# fretscanner-BRAIN.net
KiCad netlist of a schematic drawn in EAGLE
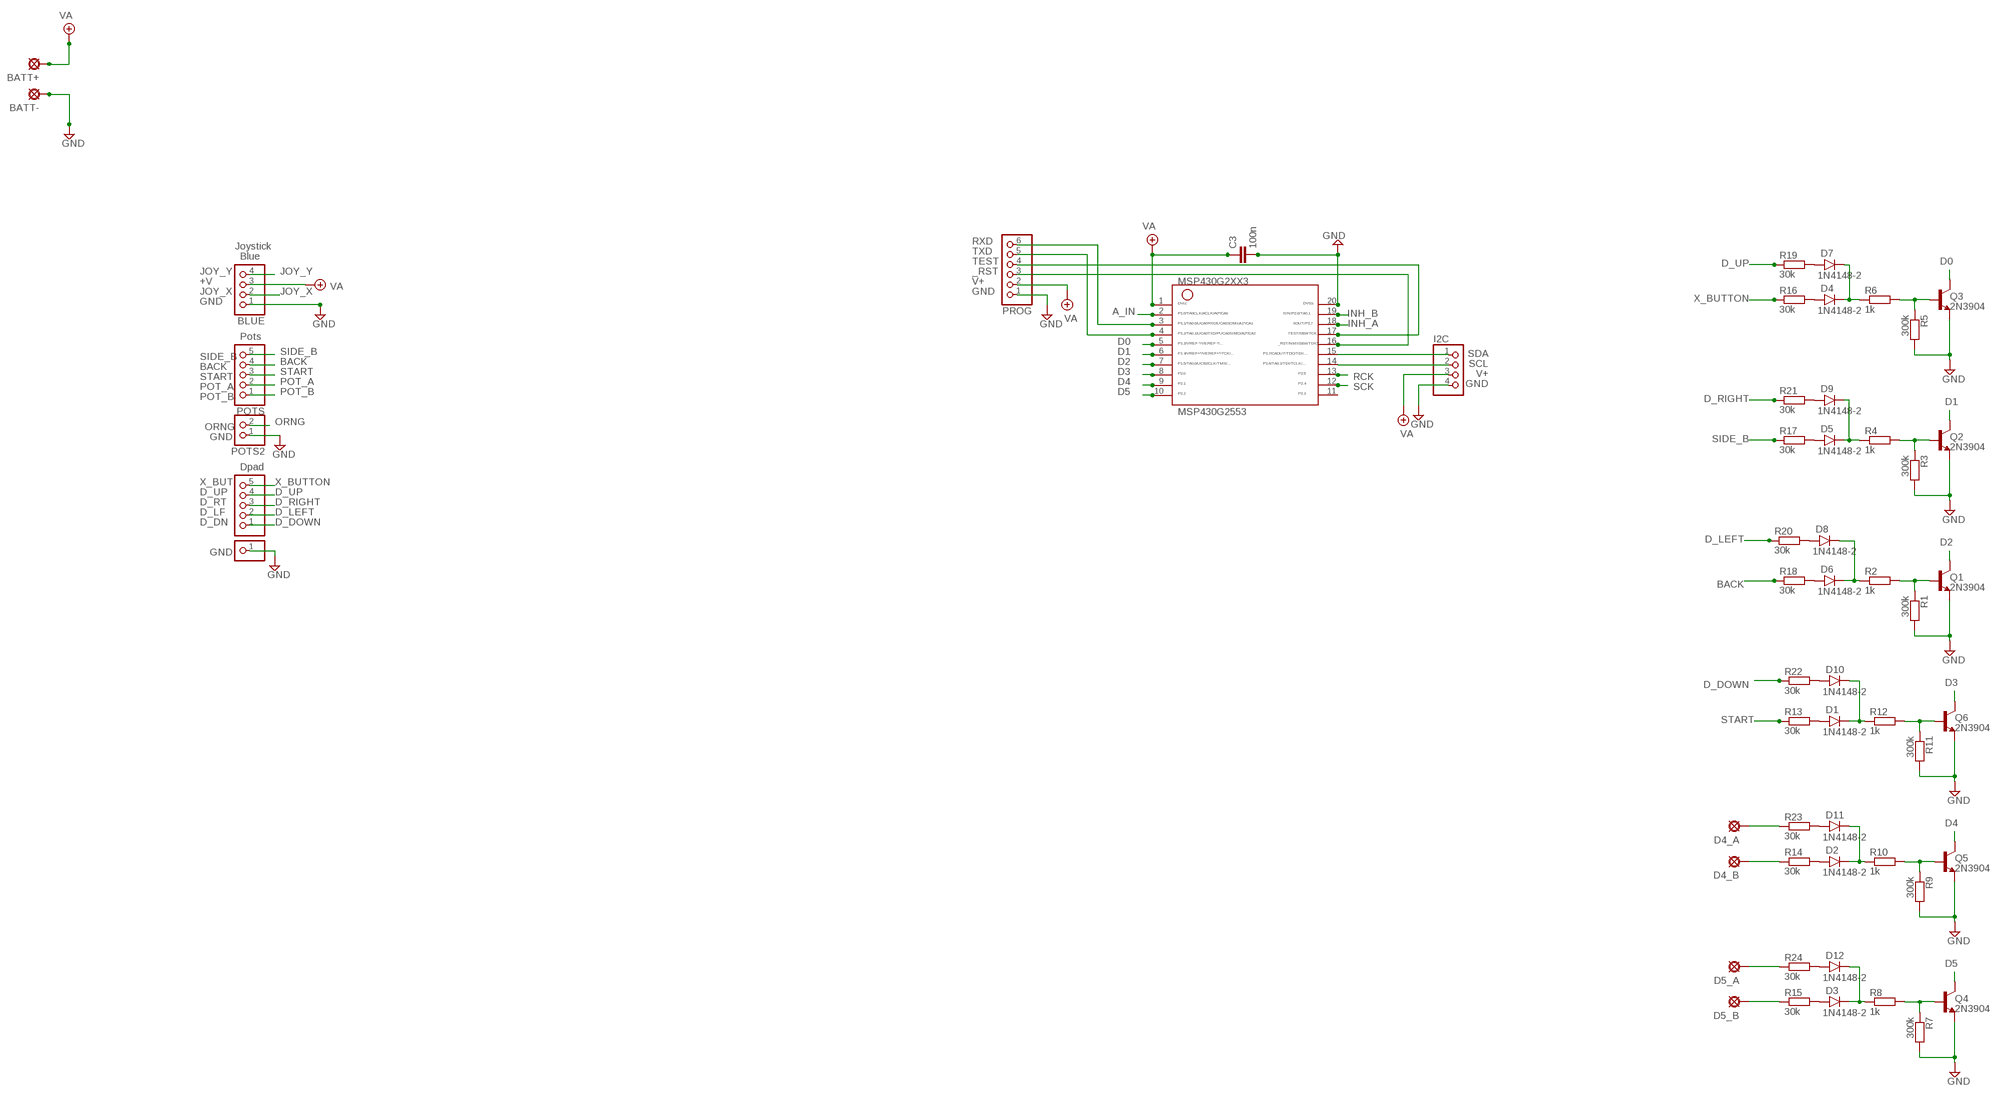
[diagram p0: schematic, sheet 1]

(export (version "E")
  (design (tool "Eeschema 10.0.6"))
  (components
    (comp (ref "BATT+")
      (value "PADL")
      (footprint "eagle-import:LONG")
      (libsource (lib "eagle-import") (part "PADL"))
    )
    (comp (ref "BATT-")
      (value "PADL")
      (footprint "eagle-import:LONG")
      (libsource (lib "eagle-import") (part "PADL"))
    )
    (comp (ref "BLUE")
      (value "PINHD-1X4")
      (footprint "eagle-import:1X04")
      (libsource (lib "eagle-import") (part "PINHD-1X4"))
    )
    (comp (ref "C3")
      (value "100n")
      (footprint "eagle-import:050X030_050_3")
      (libsource (lib "eagle-import") (part "050X030_050"))
    )
    (comp (ref "D1")
      (value "1N4148-2")
      (footprint "eagle-import:DO35-2")
      (libsource (lib "eagle-import") (part "1N4148-2"))
    )
    (comp (ref "D2")
      (value "1N4148-2")
      (footprint "eagle-import:DO35-2")
      (libsource (lib "eagle-import") (part "1N4148-2"))
    )
    (comp (ref "D3")
      (value "1N4148-2")
      (footprint "eagle-import:DO35-2")
      (libsource (lib "eagle-import") (part "1N4148-2"))
    )
    (comp (ref "D4")
      (value "1N4148-2")
      (footprint "eagle-import:DO35-2")
      (libsource (lib "eagle-import") (part "1N4148-2"))
    )
    (comp (ref "D4_A")
      (value "PAD")
      (footprint "eagle-import:SQUARE")
      (libsource (lib "eagle-import") (part "PAD"))
    )
    (comp (ref "D4_B")
      (value "PAD")
      (footprint "eagle-import:SQUARE")
      (libsource (lib "eagle-import") (part "PAD"))
    )
    (comp (ref "D5")
      (value "1N4148-2")
      (footprint "eagle-import:DO35-2")
      (libsource (lib "eagle-import") (part "1N4148-2"))
    )
    (comp (ref "D5_A")
      (value "PAD")
      (footprint "eagle-import:SQUARE")
      (libsource (lib "eagle-import") (part "PAD"))
    )
    (comp (ref "D5_B")
      (value "PAD")
      (footprint "eagle-import:SQUARE")
      (libsource (lib "eagle-import") (part "PAD"))
    )
    (comp (ref "D6")
      (value "1N4148-2")
      (footprint "eagle-import:DO35-2")
      (libsource (lib "eagle-import") (part "1N4148-2"))
    )
    (comp (ref "D7")
      (value "1N4148-2")
      (footprint "eagle-import:DO35-2")
      (libsource (lib "eagle-import") (part "1N4148-2"))
    )
    (comp (ref "D8")
      (value "1N4148-2")
      (footprint "eagle-import:DO35-2")
      (libsource (lib "eagle-import") (part "1N4148-2"))
    )
    (comp (ref "D9")
      (value "1N4148-2")
      (footprint "eagle-import:DO35-2")
      (libsource (lib "eagle-import") (part "1N4148-2"))
    )
    (comp (ref "D10")
      (value "1N4148-2")
      (footprint "eagle-import:DO35-2")
      (libsource (lib "eagle-import") (part "1N4148-2"))
    )
    (comp (ref "D11")
      (value "1N4148-2")
      (footprint "eagle-import:DO35-2")
      (libsource (lib "eagle-import") (part "1N4148-2"))
    )
    (comp (ref "D12")
      (value "1N4148-2")
      (footprint "eagle-import:DO35-2")
      (libsource (lib "eagle-import") (part "1N4148-2"))
    )
    (comp (ref "DPAD")
      (value "PINHD-1X5")
      (footprint "eagle-import:1X05")
      (libsource (lib "eagle-import") (part "PINHD-1X5"))
    )
    (comp (ref "DPAD2")
      (value "PINHD-1X1")
      (footprint "eagle-import:1X01")
      (libsource (lib "eagle-import") (part "PINHD-1X1"))
    )
    (comp (ref "I2C")
      (value "PINHD-1X4")
      (footprint "eagle-import:1X04")
      (libsource (lib "eagle-import") (part "PINHD-1X4"))
    )
    (comp (ref "MSP430G2553")
      (value "G2XX3---N20")
      (footprint "eagle-import:N20")
      (libsource (lib "eagle-import") (part "G2XX3---N20"))
    )
    (comp (ref "POTS")
      (value "PINHD-1X5")
      (footprint "eagle-import:1X05")
      (libsource (lib "eagle-import") (part "PINHD-1X5"))
    )
    (comp (ref "POTS2")
      (value "PINHD-1X2")
      (footprint "eagle-import:1X02")
      (libsource (lib "eagle-import") (part "PINHD-1X2"))
    )
    (comp (ref "PROG")
      (value "PINHD-1X6")
      (footprint "eagle-import:1X06")
      (libsource (lib "eagle-import") (part "PINHD-1X6"))
    )
    (comp (ref "Q1")
      (value "2N3904")
      (footprint "eagle-import:TO92-")
      (libsource (lib "eagle-import") (part "2N3904"))
    )
    (comp (ref "Q2")
      (value "2N3904")
      (footprint "eagle-import:TO92-")
      (libsource (lib "eagle-import") (part "2N3904"))
    )
    (comp (ref "Q3")
      (value "2N3904")
      (footprint "eagle-import:TO92-")
      (libsource (lib "eagle-import") (part "2N3904"))
    )
    (comp (ref "Q4")
      (value "2N3904")
      (footprint "eagle-import:TO92-")
      (libsource (lib "eagle-import") (part "2N3904"))
    )
    (comp (ref "Q5")
      (value "2N3904")
      (footprint "eagle-import:TO92-")
      (libsource (lib "eagle-import") (part "2N3904"))
    )
    (comp (ref "Q6")
      (value "2N3904")
      (footprint "eagle-import:TO92-")
      (libsource (lib "eagle-import") (part "2N3904"))
    )
    (comp (ref "R1")
      (value "300k")
      (footprint "eagle-import:R0207_1V")
      (libsource (lib "eagle-import") (part "6MM-EU1"))
    )
    (comp (ref "R2")
      (value "1k")
      (footprint "eagle-import:R0207_3")
      (libsource (lib "eagle-import") (part "6MM-EU"))
    )
    (comp (ref "R3")
      (value "300k")
      (footprint "eagle-import:R0207_1V")
      (libsource (lib "eagle-import") (part "6MM-EU1"))
    )
    (comp (ref "R4")
      (value "1k")
      (footprint "eagle-import:R0207_3")
      (libsource (lib "eagle-import") (part "6MM-EU"))
    )
    (comp (ref "R5")
      (value "300k")
      (footprint "eagle-import:R0207_1V")
      (libsource (lib "eagle-import") (part "6MM-EU1"))
    )
    (comp (ref "R6")
      (value "1k")
      (footprint "eagle-import:R0207_3")
      (libsource (lib "eagle-import") (part "6MM-EU"))
    )
    (comp (ref "R7")
      (value "300k")
      (footprint "eagle-import:R0207_1V")
      (libsource (lib "eagle-import") (part "6MM-EU1"))
    )
    (comp (ref "R8")
      (value "1k")
      (footprint "eagle-import:R0207_3")
      (libsource (lib "eagle-import") (part "6MM-EU"))
    )
    (comp (ref "R9")
      (value "300k")
      (footprint "eagle-import:R0207_1V")
      (libsource (lib "eagle-import") (part "6MM-EU1"))
    )
    (comp (ref "R10")
      (value "1k")
      (footprint "eagle-import:R0207_3")
      (libsource (lib "eagle-import") (part "6MM-EU"))
    )
    (comp (ref "R11")
      (value "300k")
      (footprint "eagle-import:R0207_1V")
      (libsource (lib "eagle-import") (part "6MM-EU1"))
    )
    (comp (ref "R12")
      (value "1k")
      (footprint "eagle-import:R0207_3")
      (libsource (lib "eagle-import") (part "6MM-EU"))
    )
    (comp (ref "R13")
      (value "30k")
      (footprint "eagle-import:R0207_3")
      (libsource (lib "eagle-import") (part "6MM-EU"))
    )
    (comp (ref "R14")
      (value "30k")
      (footprint "eagle-import:R0207_3")
      (libsource (lib "eagle-import") (part "6MM-EU"))
    )
    (comp (ref "R15")
      (value "30k")
      (footprint "eagle-import:R0207_3")
      (libsource (lib "eagle-import") (part "6MM-EU"))
    )
    (comp (ref "R16")
      (value "30k")
      (footprint "eagle-import:R0207_3")
      (libsource (lib "eagle-import") (part "6MM-EU"))
    )
    (comp (ref "R17")
      (value "30k")
      (footprint "eagle-import:R0207_3")
      (libsource (lib "eagle-import") (part "6MM-EU"))
    )
    (comp (ref "R18")
      (value "30k")
      (footprint "eagle-import:R0207_3")
      (libsource (lib "eagle-import") (part "6MM-EU"))
    )
    (comp (ref "R19")
      (value "30k")
      (footprint "eagle-import:R0207_3")
      (libsource (lib "eagle-import") (part "6MM-EU"))
    )
    (comp (ref "R20")
      (value "30k")
      (footprint "eagle-import:R0207_3")
      (libsource (lib "eagle-import") (part "6MM-EU"))
    )
    (comp (ref "R21")
      (value "30k")
      (footprint "eagle-import:R0207_3")
      (libsource (lib "eagle-import") (part "6MM-EU"))
    )
    (comp (ref "R22")
      (value "30k")
      (footprint "eagle-import:R0207_3")
      (libsource (lib "eagle-import") (part "6MM-EU"))
    )
    (comp (ref "R23")
      (value "30k")
      (footprint "eagle-import:R0207_3")
      (libsource (lib "eagle-import") (part "6MM-EU"))
    )
    (comp (ref "R24")
      (value "30k")
      (footprint "eagle-import:R0207_3")
      (libsource (lib "eagle-import") (part "6MM-EU"))
    )
  )
  (nets
    (net (code "1") (name "/A_IN") (class "Default")
      (node (ref "MSP430G2553") (pin "2") (pinfunction "2_2") (pintype "bidirectional"))
    )
    (net (code "2") (name "/BACK") (class "Default")
      (node (ref "POTS") (pin "4") (pinfunction "4_4") (pintype "passive"))
      (node (ref "R18") (pin "1") (pinfunction "1_1") (pintype "passive"))
    )
    (net (code "3") (name "/D0") (class "Default")
      (node (ref "MSP430G2553") (pin "5") (pinfunction "5_5") (pintype "bidirectional"))
      (node (ref "Q3") (pin "1") (pinfunction "C_1") (pintype "passive"))
    )
    (net (code "4") (name "/D1") (class "Default")
      (node (ref "MSP430G2553") (pin "6") (pinfunction "6_6") (pintype "bidirectional"))
      (node (ref "Q2") (pin "1") (pinfunction "C_1") (pintype "passive"))
    )
    (net (code "5") (name "/D2") (class "Default")
      (node (ref "MSP430G2553") (pin "7") (pinfunction "7_7") (pintype "bidirectional"))
      (node (ref "Q1") (pin "1") (pinfunction "C_1") (pintype "passive"))
    )
    (net (code "6") (name "/D3") (class "Default")
      (node (ref "MSP430G2553") (pin "8") (pinfunction "8_8") (pintype "bidirectional"))
      (node (ref "Q6") (pin "1") (pinfunction "C_1") (pintype "passive"))
    )
    (net (code "7") (name "/D4") (class "Default")
      (node (ref "MSP430G2553") (pin "9") (pinfunction "9_9") (pintype "bidirectional"))
      (node (ref "Q5") (pin "1") (pinfunction "C_1") (pintype "passive"))
    )
    (net (code "8") (name "/D5") (class "Default")
      (node (ref "MSP430G2553") (pin "10") (pinfunction "10_10") (pintype "bidirectional"))
      (node (ref "Q4") (pin "1") (pinfunction "C_1") (pintype "passive"))
    )
    (net (code "9") (name "/D_DOWN") (class "Default")
      (node (ref "DPAD") (pin "1") (pinfunction "1_1") (pintype "passive"))
      (node (ref "R22") (pin "1") (pinfunction "1_1") (pintype "passive"))
    )
    (net (code "10") (name "/D_LEFT") (class "Default")
      (node (ref "DPAD") (pin "2") (pinfunction "2_2") (pintype "passive"))
      (node (ref "R20") (pin "1") (pinfunction "1_1") (pintype "passive"))
    )
    (net (code "11") (name "/D_RIGHT") (class "Default")
      (node (ref "DPAD") (pin "3") (pinfunction "3_3") (pintype "passive"))
      (node (ref "R21") (pin "1") (pinfunction "1_1") (pintype "passive"))
    )
    (net (code "12") (name "/D_UP") (class "Default")
      (node (ref "DPAD") (pin "4") (pinfunction "4_4") (pintype "passive"))
      (node (ref "R19") (pin "1") (pinfunction "1_1") (pintype "passive"))
    )
    (net (code "13") (name "/INH_A") (class "Default")
      (node (ref "MSP430G2553") (pin "18") (pinfunction "18_18") (pintype "bidirectional"))
    )
    (net (code "14") (name "/INH_B") (class "Default")
      (node (ref "MSP430G2553") (pin "19") (pinfunction "19_19") (pintype "bidirectional"))
    )
    (net (code "15") (name "/JOY_X") (class "Default")
      (node (ref "BLUE") (pin "2") (pinfunction "2_2") (pintype "passive"))
    )
    (net (code "16") (name "/JOY_Y") (class "Default")
      (node (ref "BLUE") (pin "4") (pinfunction "4_4") (pintype "passive"))
    )
    (net (code "17") (name "/ORNG") (class "Default")
      (node (ref "POTS2") (pin "2") (pinfunction "2_2") (pintype "passive"))
    )
    (net (code "18") (name "/POT_A") (class "Default")
      (node (ref "POTS") (pin "2") (pinfunction "2_2") (pintype "passive"))
    )
    (net (code "19") (name "/POT_B") (class "Default")
      (node (ref "POTS") (pin "1") (pinfunction "1_1") (pintype "passive"))
    )
    (net (code "20") (name "/RCK") (class "Default")
      (node (ref "MSP430G2553") (pin "13") (pinfunction "13_13") (pintype "bidirectional"))
    )
    (net (code "21") (name "/SCK") (class "Default")
      (node (ref "MSP430G2553") (pin "12") (pinfunction "12_12") (pintype "bidirectional"))
    )
    (net (code "22") (name "/SIDE_B") (class "Default")
      (node (ref "POTS") (pin "5") (pinfunction "5_5") (pintype "passive"))
      (node (ref "R17") (pin "1") (pinfunction "1_1") (pintype "passive"))
    )
    (net (code "23") (name "/START") (class "Default")
      (node (ref "POTS") (pin "3") (pinfunction "3_3") (pintype "passive"))
      (node (ref "R13") (pin "1") (pinfunction "1_1") (pintype "passive"))
    )
    (net (code "24") (name "/X_BUTTON") (class "Default")
      (node (ref "DPAD") (pin "5") (pinfunction "5_5") (pintype "passive"))
      (node (ref "R16") (pin "1") (pinfunction "1_1") (pintype "passive"))
    )
    (net (code "25") (name "GND") (class "Default")
      (node (ref "BATT-") (pin "1") (pinfunction "PAD_1") (pintype "passive"))
      (node (ref "BLUE") (pin "1") (pinfunction "1_1") (pintype "passive"))
      (node (ref "C3") (pin "2") (pinfunction "2_2") (pintype "passive"))
      (node (ref "DPAD2") (pin "1") (pinfunction "1_1") (pintype "passive"))
      (node (ref "I2C") (pin "4") (pinfunction "4_4") (pintype "passive"))
      (node (ref "MSP430G2553") (pin "20") (pinfunction "20_20") (pintype "bidirectional"))
      (node (ref "POTS2") (pin "1") (pinfunction "1_1") (pintype "passive"))
      (node (ref "PROG") (pin "1") (pinfunction "1_1") (pintype "passive"))
      (node (ref "Q1") (pin "3") (pinfunction "E_3") (pintype "passive"))
      (node (ref "Q2") (pin "3") (pinfunction "E_3") (pintype "passive"))
      (node (ref "Q3") (pin "3") (pinfunction "E_3") (pintype "passive"))
      (node (ref "Q4") (pin "3") (pinfunction "E_3") (pintype "passive"))
      (node (ref "Q5") (pin "3") (pinfunction "E_3") (pintype "passive"))
      (node (ref "Q6") (pin "3") (pinfunction "E_3") (pintype "passive"))
      (node (ref "R1") (pin "2") (pinfunction "2_2") (pintype "passive"))
      (node (ref "R11") (pin "2") (pinfunction "2_2") (pintype "passive"))
      (node (ref "R3") (pin "2") (pinfunction "2_2") (pintype "passive"))
      (node (ref "R5") (pin "2") (pinfunction "2_2") (pintype "passive"))
      (node (ref "R7") (pin "2") (pinfunction "2_2") (pintype "passive"))
      (node (ref "R9") (pin "2") (pinfunction "2_2") (pintype "passive"))
    )
    (net (code "26") (name "Net-(D1-PadA)") (class "Default")
      (node (ref "D1") (pin "A") (pinfunction "A_A") (pintype "passive"))
      (node (ref "R13") (pin "2") (pinfunction "2_2") (pintype "passive"))
    )
    (net (code "27") (name "Net-(D1-PadC)") (class "Default")
      (node (ref "D1") (pin "C") (pinfunction "C_C") (pintype "passive"))
      (node (ref "D10") (pin "C") (pinfunction "C_C") (pintype "passive"))
      (node (ref "R12") (pin "1") (pinfunction "1_1") (pintype "passive"))
    )
    (net (code "28") (name "Net-(D2-PadA)") (class "Default")
      (node (ref "D2") (pin "A") (pinfunction "A_A") (pintype "passive"))
      (node (ref "R14") (pin "2") (pinfunction "2_2") (pintype "passive"))
    )
    (net (code "29") (name "Net-(D3-PadA)") (class "Default")
      (node (ref "D3") (pin "A") (pinfunction "A_A") (pintype "passive"))
      (node (ref "R15") (pin "2") (pinfunction "2_2") (pintype "passive"))
    )
    (net (code "30") (name "Net-(D4-PadA)") (class "Default")
      (node (ref "D4") (pin "A") (pinfunction "A_A") (pintype "passive"))
      (node (ref "R16") (pin "2") (pinfunction "2_2") (pintype "passive"))
    )
    (net (code "31") (name "Net-(D4-PadC)") (class "Default")
      (node (ref "D4") (pin "C") (pinfunction "C_C") (pintype "passive"))
      (node (ref "D7") (pin "C") (pinfunction "C_C") (pintype "passive"))
      (node (ref "R6") (pin "1") (pinfunction "1_1") (pintype "passive"))
    )
    (net (code "32") (name "Net-(D4_A-PAD)") (class "Default")
      (node (ref "D4_A") (pin "1") (pinfunction "PAD_1") (pintype "passive"))
      (node (ref "R23") (pin "1") (pinfunction "1_1") (pintype "passive"))
    )
    (net (code "33") (name "Net-(D4_B-PAD)") (class "Default")
      (node (ref "D4_B") (pin "1") (pinfunction "PAD_1") (pintype "passive"))
      (node (ref "R14") (pin "1") (pinfunction "1_1") (pintype "passive"))
    )
    (net (code "34") (name "Net-(D5-PadA)") (class "Default")
      (node (ref "D5") (pin "A") (pinfunction "A_A") (pintype "passive"))
      (node (ref "R17") (pin "2") (pinfunction "2_2") (pintype "passive"))
    )
    (net (code "35") (name "Net-(D5-PadC)") (class "Default")
      (node (ref "D5") (pin "C") (pinfunction "C_C") (pintype "passive"))
      (node (ref "D9") (pin "C") (pinfunction "C_C") (pintype "passive"))
      (node (ref "R4") (pin "1") (pinfunction "1_1") (pintype "passive"))
    )
    (net (code "36") (name "Net-(D5_A-PAD)") (class "Default")
      (node (ref "D5_A") (pin "1") (pinfunction "PAD_1") (pintype "passive"))
      (node (ref "R24") (pin "1") (pinfunction "1_1") (pintype "passive"))
    )
    (net (code "37") (name "Net-(D5_B-PAD)") (class "Default")
      (node (ref "D5_B") (pin "1") (pinfunction "PAD_1") (pintype "passive"))
      (node (ref "R15") (pin "1") (pinfunction "1_1") (pintype "passive"))
    )
    (net (code "38") (name "Net-(D6-PadA)") (class "Default")
      (node (ref "D6") (pin "A") (pinfunction "A_A") (pintype "passive"))
      (node (ref "R18") (pin "2") (pinfunction "2_2") (pintype "passive"))
    )
    (net (code "39") (name "Net-(D6-PadC)") (class "Default")
      (node (ref "D6") (pin "C") (pinfunction "C_C") (pintype "passive"))
      (node (ref "D8") (pin "C") (pinfunction "C_C") (pintype "passive"))
      (node (ref "R2") (pin "1") (pinfunction "1_1") (pintype "passive"))
    )
    (net (code "40") (name "Net-(D7-PadA)") (class "Default")
      (node (ref "D7") (pin "A") (pinfunction "A_A") (pintype "passive"))
      (node (ref "R19") (pin "2") (pinfunction "2_2") (pintype "passive"))
    )
    (net (code "41") (name "Net-(D8-PadA)") (class "Default")
      (node (ref "D8") (pin "A") (pinfunction "A_A") (pintype "passive"))
      (node (ref "R20") (pin "2") (pinfunction "2_2") (pintype "passive"))
    )
    (net (code "42") (name "Net-(D9-PadA)") (class "Default")
      (node (ref "D9") (pin "A") (pinfunction "A_A") (pintype "passive"))
      (node (ref "R21") (pin "2") (pinfunction "2_2") (pintype "passive"))
    )
    (net (code "43") (name "Net-(D10-PadA)") (class "Default")
      (node (ref "D10") (pin "A") (pinfunction "A_A") (pintype "passive"))
      (node (ref "R22") (pin "2") (pinfunction "2_2") (pintype "passive"))
    )
    (net (code "44") (name "Net-(D11-PadA)") (class "Default")
      (node (ref "D11") (pin "A") (pinfunction "A_A") (pintype "passive"))
      (node (ref "R23") (pin "2") (pinfunction "2_2") (pintype "passive"))
    )
    (net (code "45") (name "Net-(D11-PadC)") (class "Default")
      (node (ref "D11") (pin "C") (pinfunction "C_C") (pintype "passive"))
      (node (ref "D2") (pin "C") (pinfunction "C_C") (pintype "passive"))
      (node (ref "R10") (pin "1") (pinfunction "1_1") (pintype "passive"))
    )
    (net (code "46") (name "Net-(D12-PadA)") (class "Default")
      (node (ref "D12") (pin "A") (pinfunction "A_A") (pintype "passive"))
      (node (ref "R24") (pin "2") (pinfunction "2_2") (pintype "passive"))
    )
    (net (code "47") (name "Net-(D12-PadC)") (class "Default")
      (node (ref "D12") (pin "C") (pinfunction "C_C") (pintype "passive"))
      (node (ref "D3") (pin "C") (pinfunction "C_C") (pintype "passive"))
      (node (ref "R8") (pin "1") (pinfunction "1_1") (pintype "passive"))
    )
    (net (code "48") (name "Net-(I2C-Pad1)") (class "Default")
      (node (ref "I2C") (pin "1") (pinfunction "1_1") (pintype "passive"))
      (node (ref "MSP430G2553") (pin "15") (pinfunction "15_15") (pintype "bidirectional"))
    )
    (net (code "49") (name "Net-(I2C-Pad2)") (class "Default")
      (node (ref "I2C") (pin "2") (pinfunction "2_2") (pintype "passive"))
      (node (ref "MSP430G2553") (pin "14") (pinfunction "14_14") (pintype "bidirectional"))
    )
    (net (code "50") (name "Net-(MSP430G2553-Pad3)") (class "Default")
      (node (ref "MSP430G2553") (pin "3") (pinfunction "3_3") (pintype "bidirectional"))
      (node (ref "PROG") (pin "6") (pinfunction "6_6") (pintype "passive"))
    )
    (net (code "51") (name "Net-(MSP430G2553-Pad4)") (class "Default")
      (node (ref "MSP430G2553") (pin "4") (pinfunction "4_4") (pintype "bidirectional"))
      (node (ref "PROG") (pin "5") (pinfunction "5_5") (pintype "passive"))
    )
    (net (code "52") (name "Net-(MSP430G2553-Pad16)") (class "Default")
      (node (ref "MSP430G2553") (pin "16") (pinfunction "16_16") (pintype "bidirectional"))
      (node (ref "PROG") (pin "3") (pinfunction "3_3") (pintype "passive"))
    )
    (net (code "53") (name "Net-(MSP430G2553-Pad17)") (class "Default")
      (node (ref "MSP430G2553") (pin "17") (pinfunction "17_17") (pintype "bidirectional"))
      (node (ref "PROG") (pin "4") (pinfunction "4_4") (pintype "passive"))
    )
    (net (code "54") (name "Net-(Q1-B)") (class "Default")
      (node (ref "Q1") (pin "2") (pinfunction "B_2") (pintype "passive"))
      (node (ref "R1") (pin "1") (pinfunction "1_1") (pintype "passive"))
      (node (ref "R2") (pin "2") (pinfunction "2_2") (pintype "passive"))
    )
    (net (code "55") (name "Net-(Q2-B)") (class "Default")
      (node (ref "Q2") (pin "2") (pinfunction "B_2") (pintype "passive"))
      (node (ref "R3") (pin "1") (pinfunction "1_1") (pintype "passive"))
      (node (ref "R4") (pin "2") (pinfunction "2_2") (pintype "passive"))
    )
    (net (code "56") (name "Net-(Q3-B)") (class "Default")
      (node (ref "Q3") (pin "2") (pinfunction "B_2") (pintype "passive"))
      (node (ref "R5") (pin "1") (pinfunction "1_1") (pintype "passive"))
      (node (ref "R6") (pin "2") (pinfunction "2_2") (pintype "passive"))
    )
    (net (code "57") (name "Net-(Q4-B)") (class "Default")
      (node (ref "Q4") (pin "2") (pinfunction "B_2") (pintype "passive"))
      (node (ref "R7") (pin "1") (pinfunction "1_1") (pintype "passive"))
      (node (ref "R8") (pin "2") (pinfunction "2_2") (pintype "passive"))
    )
    (net (code "58") (name "Net-(Q5-B)") (class "Default")
      (node (ref "Q5") (pin "2") (pinfunction "B_2") (pintype "passive"))
      (node (ref "R10") (pin "2") (pinfunction "2_2") (pintype "passive"))
      (node (ref "R9") (pin "1") (pinfunction "1_1") (pintype "passive"))
    )
    (net (code "59") (name "Net-(Q6-B)") (class "Default")
      (node (ref "Q6") (pin "2") (pinfunction "B_2") (pintype "passive"))
      (node (ref "R11") (pin "1") (pinfunction "1_1") (pintype "passive"))
      (node (ref "R12") (pin "2") (pinfunction "2_2") (pintype "passive"))
    )
    (net (code "60") (name "VA") (class "Default")
      (node (ref "BATT+") (pin "1") (pinfunction "PAD_1") (pintype "passive"))
      (node (ref "BLUE") (pin "3") (pinfunction "3_3") (pintype "passive"))
      (node (ref "C3") (pin "1") (pinfunction "1_1") (pintype "passive"))
      (node (ref "I2C") (pin "3") (pinfunction "3_3") (pintype "passive"))
      (node (ref "MSP430G2553") (pin "1") (pinfunction "1_1") (pintype "bidirectional"))
      (node (ref "PROG") (pin "2") (pinfunction "2_2") (pintype "passive"))
    )
    (net (code "61") (name "unconnected-(MSP430G2553-Pad11)") (class "Default")
      (node (ref "MSP430G2553") (pin "11") (pinfunction "11_11") (pintype "bidirectional"))
    )
  )
)
